# SerialLink.net
KiCad netlist of a schematic drawn in EAGLE
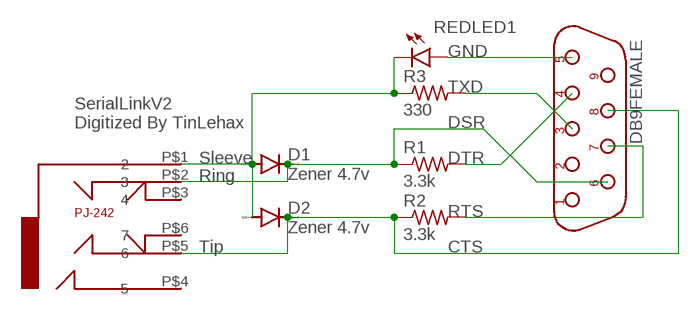
[diagram p0: schematic, sheet 1]

(export (version "E")
  (design (tool "Eeschema 10.0.6"))
  (components
    (comp (ref "D1")
      (value "Zener 4.7v")
      (footprint "eagle-import:SOD80C")
      (libsource (lib "eagle-import") (part "PMLL4150"))
    )
    (comp (ref "D2")
      (value "Zener 4.7v")
      (footprint "eagle-import:SOD80C")
      (libsource (lib "eagle-import") (part "PMLL4150"))
    )
    (comp (ref "DB9FEMALE")
      (value "DB9F/90")
      (footprint "eagle-import:D-09F_90")
      (libsource (lib "eagle-import") (part "DB9F/90"))
    )
    (comp (ref "R1")
      (value "3.3k")
      (footprint "eagle-import:R0805")
      (libsource (lib "eagle-import") (part "R-US_R0805"))
    )
    (comp (ref "R2")
      (value "3.3k")
      (footprint "eagle-import:R0805")
      (libsource (lib "eagle-import") (part "R-US_R0805"))
    )
    (comp (ref "R3")
      (value "330")
      (footprint "eagle-import:R0805")
      (libsource (lib "eagle-import") (part "R-US_R0805"))
    )
    (comp (ref "REDLED1")
      (value "LED1206")
      (footprint "eagle-import:LED-1206")
      (libsource (lib "eagle-import") (part "LED1206"))
    )
    (comp (ref "U$2")
      (value "PJ-242")
      (footprint "eagle-import:PJ-242")
      (fields (field (name "PARTNO") "PJ-242 2.5mm headphone jack socket 6 pin"))
      (libsource (lib "eagle-import") (part "PJ-242"))
    )
  )
  (nets
    (net (code "1") (name "Net-(DB9FEMALE-Pad3)") (class "Default")
      (node (ref "DB9FEMALE") (pin "3") (pinfunction "3_3") (pintype "passive"))
      (node (ref "R3") (pin "2") (pinfunction "2_2") (pintype "passive"))
    )
    (net (code "2") (name "Net-(DB9FEMALE-Pad4)") (class "Default")
      (node (ref "DB9FEMALE") (pin "4") (pinfunction "4_4") (pintype "passive"))
      (node (ref "R1") (pin "2") (pinfunction "2_2") (pintype "passive"))
    )
    (net (code "3") (name "Net-(DB9FEMALE-Pad5)") (class "Default")
      (node (ref "DB9FEMALE") (pin "5") (pinfunction "5_5") (pintype "passive"))
      (node (ref "REDLED1") (pin "A") (pinfunction "A_A") (pintype "passive"))
    )
    (net (code "4") (name "Net-(DB9FEMALE-Pad7)") (class "Default")
      (node (ref "DB9FEMALE") (pin "7") (pinfunction "7_7") (pintype "passive"))
      (node (ref "R2") (pin "2") (pinfunction "2_2") (pintype "passive"))
    )
    (net (code "5") (name "Net-(U$2-2)") (class "Default")
      (node (ref "D1") (pin "A") (pinfunction "A_A") (pintype "passive"))
      (node (ref "D2") (pin "A") (pinfunction "A_A") (pintype "passive"))
      (node (ref "R3") (pin "1") (pinfunction "1_1") (pintype "passive"))
      (node (ref "REDLED1") (pin "C") (pinfunction "C_C") (pintype "passive"))
      (node (ref "U$2") (pin "P$1") (pinfunction "2_P$1") (pintype "bidirectional"))
    )
    (net (code "6") (name "Net-(U$2-3)") (class "Default")
      (node (ref "D1") (pin "C") (pinfunction "C_C") (pintype "passive"))
      (node (ref "DB9FEMALE") (pin "6") (pinfunction "6_6") (pintype "passive"))
      (node (ref "R1") (pin "1") (pinfunction "1_1") (pintype "passive"))
      (node (ref "U$2") (pin "P$2") (pinfunction "3_P$2") (pintype "bidirectional"))
    )
    (net (code "7") (name "Net-(U$2-6)") (class "Default")
      (node (ref "D2") (pin "C") (pinfunction "C_C") (pintype "passive"))
      (node (ref "DB9FEMALE") (pin "8") (pinfunction "8_8") (pintype "passive"))
      (node (ref "R2") (pin "1") (pinfunction "1_1") (pintype "passive"))
      (node (ref "U$2") (pin "P$5") (pinfunction "6_P$5") (pintype "bidirectional"))
    )
    (net (code "8") (name "unconnected-(DB9FEMALE-Pad1)") (class "Default")
      (node (ref "DB9FEMALE") (pin "1") (pinfunction "1_1") (pintype "passive"))
    )
    (net (code "9") (name "unconnected-(DB9FEMALE-Pad2)") (class "Default")
      (node (ref "DB9FEMALE") (pin "2") (pinfunction "2_2") (pintype "passive"))
    )
    (net (code "10") (name "unconnected-(DB9FEMALE-Pad9)") (class "Default")
      (node (ref "DB9FEMALE") (pin "9") (pinfunction "9_9") (pintype "passive"))
    )
    (net (code "11") (name "unconnected-(U$2-4-PadP$3)") (class "Default")
      (node (ref "U$2") (pin "P$3") (pinfunction "4_P$3") (pintype "bidirectional"))
    )
    (net (code "12") (name "unconnected-(U$2-5-PadP$4)") (class "Default")
      (node (ref "U$2") (pin "P$4") (pinfunction "5_P$4") (pintype "bidirectional"))
    )
    (net (code "13") (name "unconnected-(U$2-7-PadP$6)") (class "Default")
      (node (ref "U$2") (pin "P$6") (pinfunction "7_P$6") (pintype "bidirectional"))
    )
  )
)
